# hail-wifi.net
KiCad netlist of a schematic drawn in EAGLE
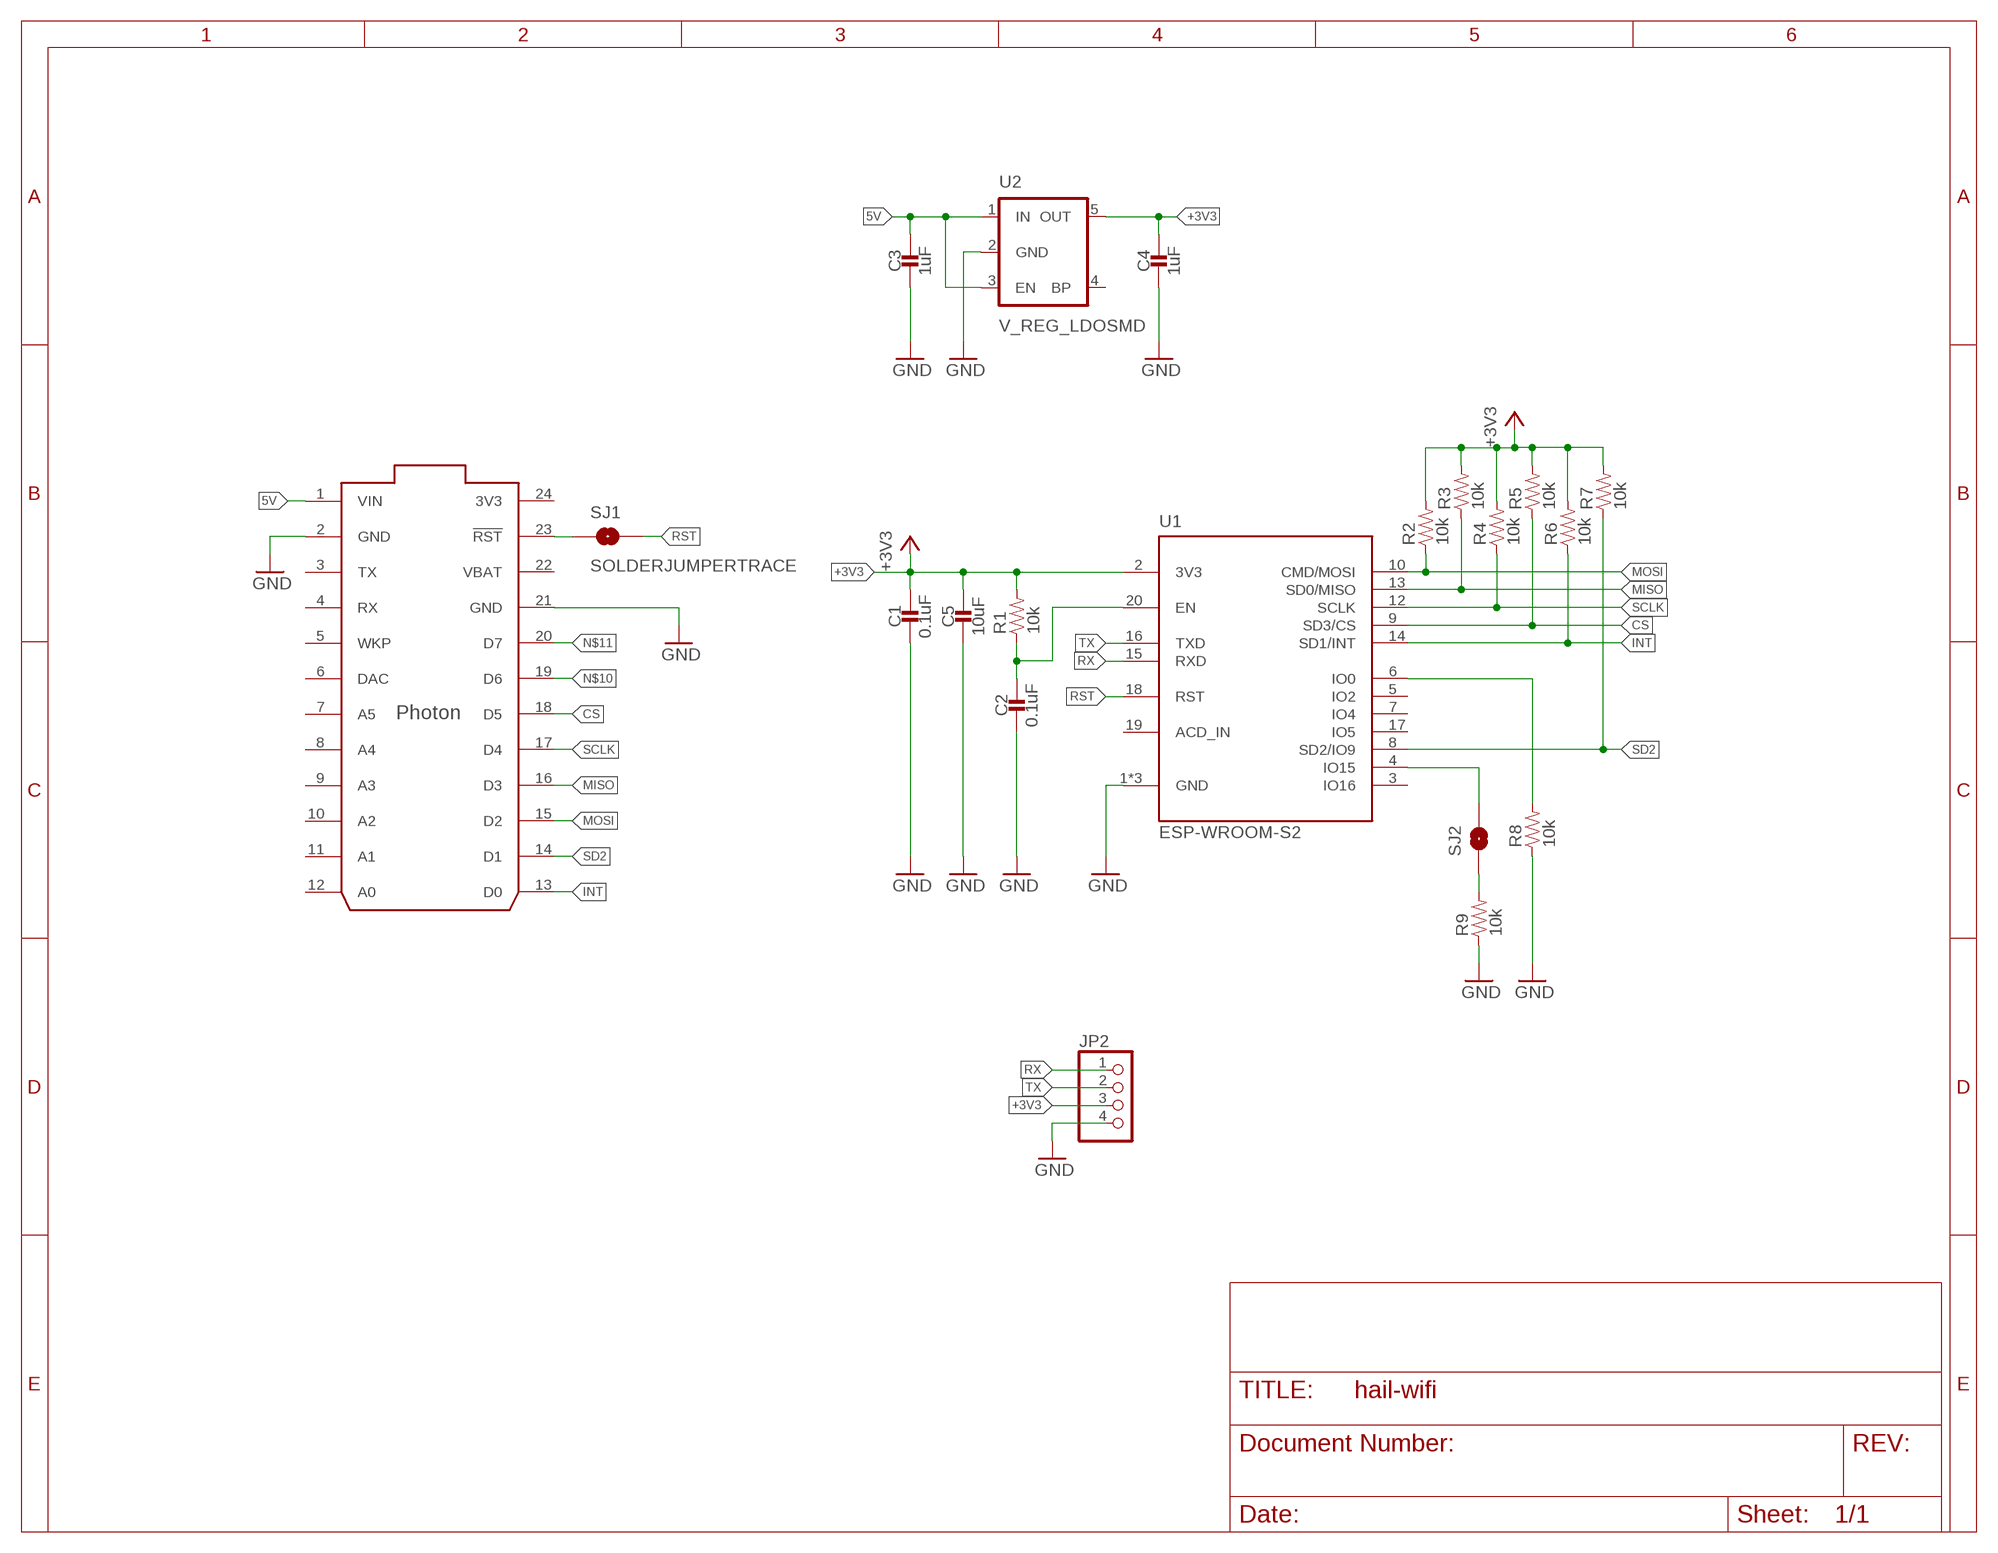
[diagram p0: schematic, sheet 1]

(export (version "E")
  (design (tool "Eeschema 10.0.6"))
  (components
    (comp (ref "C1")
      (value "0.1uF")
      (footprint "eagle-import:0603_CAP")
      (libsource (lib "eagle-import") (part "CAPACITOR0603_CAP"))
    )
    (comp (ref "C2")
      (value "0.1uF")
      (footprint "eagle-import:0603_CAP")
      (libsource (lib "eagle-import") (part "CAPACITOR0603_CAP"))
    )
    (comp (ref "C3")
      (value "1uF")
      (footprint "eagle-import:0603_CAP")
      (libsource (lib "eagle-import") (part "CAPACITOR0603_CAP"))
    )
    (comp (ref "C4")
      (value "1uF")
      (footprint "eagle-import:0603_CAP")
      (libsource (lib "eagle-import") (part "CAPACITOR0603_CAP"))
    )
    (comp (ref "C5")
      (value "10uF")
      (footprint "eagle-import:0603_CAP")
      (libsource (lib "eagle-import") (part "CAPACITOR0603_CAP"))
    )
    (comp (ref "JP2")
      (value "PINHD-1X4/90")
      (footprint "eagle-import:1X04_90")
      (libsource (lib "eagle-import") (part "PINHD-1X4/90"))
    )
    (comp (ref "R1")
      (value "10k")
      (footprint "eagle-import:0603-RES")
      (libsource (lib "eagle-import") (part "RESISTOR0603_RES"))
    )
    (comp (ref "R2")
      (value "10k")
      (footprint "eagle-import:0603-RES")
      (libsource (lib "eagle-import") (part "RESISTOR0603_RES"))
    )
    (comp (ref "R3")
      (value "10k")
      (footprint "eagle-import:0603-RES")
      (libsource (lib "eagle-import") (part "RESISTOR0603_RES"))
    )
    (comp (ref "R4")
      (value "10k")
      (footprint "eagle-import:0603-RES")
      (libsource (lib "eagle-import") (part "RESISTOR0603_RES"))
    )
    (comp (ref "R5")
      (value "10k")
      (footprint "eagle-import:0603-RES")
      (libsource (lib "eagle-import") (part "RESISTOR0603_RES"))
    )
    (comp (ref "R6")
      (value "10k")
      (footprint "eagle-import:0603-RES")
      (libsource (lib "eagle-import") (part "RESISTOR0603_RES"))
    )
    (comp (ref "R7")
      (value "10k")
      (footprint "eagle-import:0603-RES")
      (libsource (lib "eagle-import") (part "RESISTOR0603_RES"))
    )
    (comp (ref "R8")
      (value "10k")
      (footprint "eagle-import:0603-RES")
      (libsource (lib "eagle-import") (part "RESISTOR0603_RES"))
    )
    (comp (ref "R9")
      (value "10k")
      (footprint "eagle-import:0603-RES")
      (libsource (lib "eagle-import") (part "RESISTOR0603_RES"))
    )
    (comp (ref "SJ1")
      (value "SOLDERJUMPERTRACE")
      (footprint "eagle-import:SJ_2S-TRACE")
      (libsource (lib "eagle-import") (part "SOLDERJUMPERTRACE"))
    )
    (comp (ref "SJ2")
      (value "SOLDERJUMPERNO")
      (footprint "eagle-import:SJ_2S-NO")
      (libsource (lib "eagle-import") (part "SOLDERJUMPERNO"))
    )
    (comp (ref "U1")
      (value "ESP-WROOM-S2")
      (footprint "eagle-import:ESP-WROOM-S2")
      (libsource (lib "eagle-import") (part "ESP-WROOM-S2"))
    )
    (comp (ref "U2")
      (value "V_REG_LDOSMD")
      (footprint "eagle-import:SOT23-5")
      (libsource (lib "eagle-import") (part "V_REG_LDOSMD"))
    )
    (comp (ref "U3")
      (value "PHOTON_WITH_HEADERS")
      (footprint "eagle-import:PHOTON")
      (libsource (lib "eagle-import") (part "PHOTON_WITH_HEADERS"))
    )
  )
  (nets
    (net (code "1") (name "+3V3") (class "Default")
      (node (ref "C1") (pin "1") (pinfunction "1_1") (pintype "bidirectional"))
      (node (ref "C4") (pin "1") (pinfunction "1_1") (pintype "bidirectional"))
      (node (ref "C5") (pin "1") (pinfunction "1_1") (pintype "bidirectional"))
      (node (ref "JP2") (pin "3") (pinfunction "3_3") (pintype "passive"))
      (node (ref "R1") (pin "2") (pinfunction "2_2") (pintype "passive"))
      (node (ref "R2") (pin "2") (pinfunction "2_2") (pintype "passive"))
      (node (ref "R3") (pin "2") (pinfunction "2_2") (pintype "passive"))
      (node (ref "R4") (pin "2") (pinfunction "2_2") (pintype "passive"))
      (node (ref "R5") (pin "2") (pinfunction "2_2") (pintype "passive"))
      (node (ref "R6") (pin "2") (pinfunction "2_2") (pintype "passive"))
      (node (ref "R7") (pin "2") (pinfunction "2_2") (pintype "passive"))
      (node (ref "U1") (pin "2") (pinfunction "3V3_2") (pintype "bidirectional"))
      (node (ref "U2") (pin "5") (pinfunction "OUT_5") (pintype "passive"))
    )
    (net (code "2") (name "/3V3") (class "Default")
      (node (ref "U3") (pin "24") (pinfunction "3V3_24") (pintype "power_in"))
    )
    (net (code "3") (name "/VBAT") (class "Default")
      (node (ref "U3") (pin "22") (pinfunction "VBAT_22") (pintype "power_in"))
    )
    (net (code "4") (name "5V") (class "Default")
      (node (ref "C3") (pin "1") (pinfunction "1_1") (pintype "bidirectional"))
      (node (ref "U2") (pin "1") (pinfunction "IN_1") (pintype "input"))
      (node (ref "U2") (pin "3") (pinfunction "EN_3") (pintype "input"))
      (node (ref "U3") (pin "1") (pinfunction "VIN_1") (pintype "power_in"))
    )
    (net (code "5") (name "CS") (class "Default")
      (node (ref "R5") (pin "1") (pinfunction "1_1") (pintype "passive"))
      (node (ref "U1") (pin "9") (pinfunction "SD3/CS_9") (pintype "bidirectional"))
      (node (ref "U3") (pin "18") (pinfunction "D5_18") (pintype "bidirectional"))
    )
    (net (code "6") (name "GND") (class "Default")
      (node (ref "C1") (pin "2") (pinfunction "2_2") (pintype "bidirectional"))
      (node (ref "C2") (pin "2") (pinfunction "2_2") (pintype "bidirectional"))
      (node (ref "C3") (pin "2") (pinfunction "2_2") (pintype "bidirectional"))
      (node (ref "C4") (pin "2") (pinfunction "2_2") (pintype "bidirectional"))
      (node (ref "C5") (pin "2") (pinfunction "2_2") (pintype "bidirectional"))
      (node (ref "JP2") (pin "4") (pinfunction "4_4") (pintype "passive"))
      (node (ref "R8") (pin "1") (pinfunction "1_1") (pintype "passive"))
      (node (ref "R9") (pin "1") (pinfunction "1_1") (pintype "passive"))
      (node (ref "U1") (pin "1") (pinfunction "GND_1") (pintype "bidirectional"))
      (node (ref "U1") (pin "11") (pinfunction "GND_11") (pintype "bidirectional"))
      (node (ref "U1") (pin "21") (pinfunction "GND_21") (pintype "bidirectional"))
      (node (ref "U2") (pin "2") (pinfunction "GND_2") (pintype "input"))
      (node (ref "U3") (pin "2") (pinfunction "GND_2") (pintype "power_in"))
      (node (ref "U3") (pin "21") (pinfunction "GND_21") (pintype "power_in"))
    )
    (net (code "7") (name "INT") (class "Default")
      (node (ref "R6") (pin "1") (pinfunction "1_1") (pintype "passive"))
      (node (ref "U1") (pin "14") (pinfunction "SD1/INT_14") (pintype "bidirectional"))
      (node (ref "U3") (pin "13") (pinfunction "D0_13") (pintype "bidirectional"))
    )
    (net (code "8") (name "MISO") (class "Default")
      (node (ref "R3") (pin "1") (pinfunction "1_1") (pintype "passive"))
      (node (ref "U1") (pin "13") (pinfunction "SD0/MISO_13") (pintype "bidirectional"))
      (node (ref "U3") (pin "16") (pinfunction "D3_16") (pintype "bidirectional"))
    )
    (net (code "9") (name "MOSI") (class "Default")
      (node (ref "R2") (pin "1") (pinfunction "1_1") (pintype "passive"))
      (node (ref "U1") (pin "10") (pinfunction "CMD/MOSI_10") (pintype "bidirectional"))
      (node (ref "U3") (pin "15") (pinfunction "D2_15") (pintype "bidirectional"))
    )
    (net (code "10") (name "N$10") (class "Default")
      (node (ref "U3") (pin "19") (pinfunction "D6_19") (pintype "bidirectional"))
    )
    (net (code "11") (name "N$11") (class "Default")
      (node (ref "U3") (pin "20") (pinfunction "D7_20") (pintype "bidirectional"))
    )
    (net (code "12") (name "Net-(R9-Pad2)") (class "Default")
      (node (ref "R9") (pin "2") (pinfunction "2_2") (pintype "passive"))
      (node (ref "SJ2") (pin "1") (pinfunction "1_1") (pintype "passive"))
    )
    (net (code "13") (name "Net-(U1-EN)") (class "Default")
      (node (ref "C2") (pin "1") (pinfunction "1_1") (pintype "bidirectional"))
      (node (ref "R1") (pin "1") (pinfunction "1_1") (pintype "passive"))
      (node (ref "U1") (pin "20") (pinfunction "EN_20") (pintype "bidirectional"))
    )
    (net (code "14") (name "Net-(U1-IO0)") (class "Default")
      (node (ref "R8") (pin "2") (pinfunction "2_2") (pintype "passive"))
      (node (ref "U1") (pin "6") (pinfunction "IO0_6") (pintype "bidirectional"))
    )
    (net (code "15") (name "Net-(U1-IO15)") (class "Default")
      (node (ref "SJ2") (pin "2") (pinfunction "2_2") (pintype "passive"))
      (node (ref "U1") (pin "4") (pinfunction "IO15_4") (pintype "bidirectional"))
    )
    (net (code "16") (name "Net-(U3-~{RST})") (class "Default")
      (node (ref "SJ1") (pin "1") (pinfunction "1_1") (pintype "passive"))
      (node (ref "U3") (pin "23") (pinfunction "~{RST}_23") (pintype "bidirectional"))
    )
    (net (code "17") (name "RST") (class "Default")
      (node (ref "SJ1") (pin "2") (pinfunction "2_2") (pintype "passive"))
      (node (ref "U1") (pin "18") (pinfunction "RST_18") (pintype "bidirectional"))
    )
    (net (code "18") (name "RX") (class "Default")
      (node (ref "JP2") (pin "1") (pinfunction "1_1") (pintype "passive"))
      (node (ref "U1") (pin "15") (pinfunction "RXD_15") (pintype "bidirectional"))
    )
    (net (code "19") (name "SCLK") (class "Default")
      (node (ref "R4") (pin "1") (pinfunction "1_1") (pintype "passive"))
      (node (ref "U1") (pin "12") (pinfunction "SCLK_12") (pintype "bidirectional"))
      (node (ref "U3") (pin "17") (pinfunction "D4_17") (pintype "bidirectional"))
    )
    (net (code "20") (name "SD2") (class "Default")
      (node (ref "R7") (pin "1") (pinfunction "1_1") (pintype "passive"))
      (node (ref "U1") (pin "8") (pinfunction "SD2/IO9_8") (pintype "bidirectional"))
      (node (ref "U3") (pin "14") (pinfunction "D1_14") (pintype "bidirectional"))
    )
    (net (code "21") (name "TX") (class "Default")
      (node (ref "JP2") (pin "2") (pinfunction "2_2") (pintype "passive"))
      (node (ref "U1") (pin "16") (pinfunction "TXD_16") (pintype "bidirectional"))
    )
    (net (code "22") (name "unconnected-(U1-ACD_IN-Pad19)") (class "Default")
      (node (ref "U1") (pin "19") (pinfunction "ACD_IN_19") (pintype "bidirectional"))
    )
    (net (code "23") (name "unconnected-(U1-IO2-Pad5)") (class "Default")
      (node (ref "U1") (pin "5") (pinfunction "IO2_5") (pintype "bidirectional"))
    )
    (net (code "24") (name "unconnected-(U1-IO4-Pad7)") (class "Default")
      (node (ref "U1") (pin "7") (pinfunction "IO4_7") (pintype "bidirectional"))
    )
    (net (code "25") (name "unconnected-(U1-IO5-Pad17)") (class "Default")
      (node (ref "U1") (pin "17") (pinfunction "IO5_17") (pintype "bidirectional"))
    )
    (net (code "26") (name "unconnected-(U1-IO16-Pad3)") (class "Default")
      (node (ref "U1") (pin "3") (pinfunction "IO16_3") (pintype "bidirectional"))
    )
    (net (code "27") (name "unconnected-(U2-BP-Pad4)") (class "Default")
      (node (ref "U2") (pin "4") (pinfunction "BP_4") (pintype "input"))
    )
    (net (code "28") (name "unconnected-(U3-A0-Pad12)") (class "Default")
      (node (ref "U3") (pin "12") (pinfunction "A0_12") (pintype "bidirectional"))
    )
    (net (code "29") (name "unconnected-(U3-A1-Pad11)") (class "Default")
      (node (ref "U3") (pin "11") (pinfunction "A1_11") (pintype "bidirectional"))
    )
    (net (code "30") (name "unconnected-(U3-A2-Pad10)") (class "Default")
      (node (ref "U3") (pin "10") (pinfunction "A2_10") (pintype "bidirectional"))
    )
    (net (code "31") (name "unconnected-(U3-A3-Pad9)") (class "Default")
      (node (ref "U3") (pin "9") (pinfunction "A3_9") (pintype "bidirectional"))
    )
    (net (code "32") (name "unconnected-(U3-A4-Pad8)") (class "Default")
      (node (ref "U3") (pin "8") (pinfunction "A4_8") (pintype "bidirectional"))
    )
    (net (code "33") (name "unconnected-(U3-A5-Pad7)") (class "Default")
      (node (ref "U3") (pin "7") (pinfunction "A5_7") (pintype "bidirectional"))
    )
    (net (code "34") (name "unconnected-(U3-DAC-Pad6)") (class "Default")
      (node (ref "U3") (pin "6") (pinfunction "DAC_6") (pintype "bidirectional"))
    )
    (net (code "35") (name "unconnected-(U3-RX-Pad4)") (class "Default")
      (node (ref "U3") (pin "4") (pinfunction "RX_4") (pintype "bidirectional"))
    )
    (net (code "36") (name "unconnected-(U3-TX-Pad3)") (class "Default")
      (node (ref "U3") (pin "3") (pinfunction "TX_3") (pintype "bidirectional"))
    )
    (net (code "37") (name "unconnected-(U3-WKP-Pad5)") (class "Default")
      (node (ref "U3") (pin "5") (pinfunction "WKP_5") (pintype "bidirectional"))
    )
  )
)
